# p4b-leds.net
KiCad netlist of a schematic drawn in Altium Designer
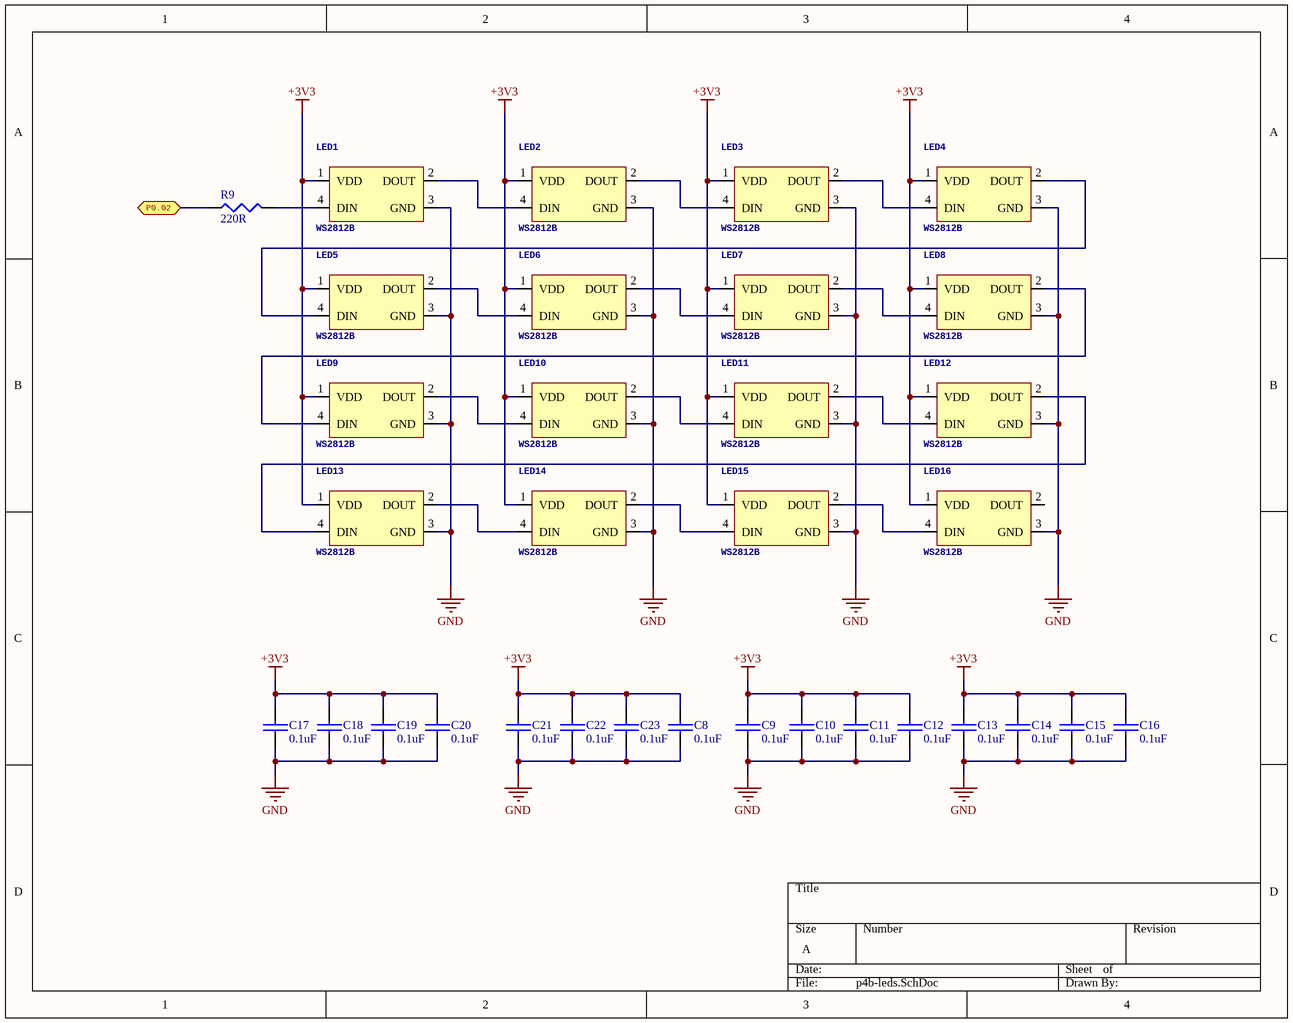
[diagram p0: p4b-leds.SchDoc]

(export (version "E")
  (design (tool "Eeschema 10.0.6"))
  (components
    (comp (ref "C8")
      (value "0.1uF")
      (footprint "C0603")
      (description "CAP, CER, 0.1UF, 6.3v, 10%, X5R, 0603")
      (fields (field (name "Comment") "VALUE"))
      (libsource (lib "bdk-schlib") (part "CAP-0.1UF-0603"))
    )
    (comp (ref "C9")
      (value "0.1uF")
      (footprint "C0603")
      (description "CAP, CER, 0.1UF, 6.3v, 10%, X5R, 0603")
      (fields (field (name "Comment") "VALUE"))
      (libsource (lib "bdk-schlib") (part "CAP-0.1UF-0603"))
    )
    (comp (ref "C10")
      (value "0.1uF")
      (footprint "C0603")
      (description "CAP, CER, 0.1UF, 6.3v, 10%, X5R, 0603")
      (fields (field (name "Comment") "VALUE"))
      (libsource (lib "bdk-schlib") (part "CAP-0.1UF-0603"))
    )
    (comp (ref "C11")
      (value "0.1uF")
      (footprint "C0603")
      (description "CAP, CER, 0.1UF, 6.3v, 10%, X5R, 0603")
      (fields (field (name "Comment") "VALUE"))
      (libsource (lib "bdk-schlib") (part "CAP-0.1UF-0603"))
    )
    (comp (ref "C12")
      (value "0.1uF")
      (footprint "C0603")
      (description "CAP, CER, 0.1UF, 6.3v, 10%, X5R, 0603")
      (fields (field (name "Comment") "VALUE"))
      (libsource (lib "bdk-schlib") (part "CAP-0.1UF-0603"))
    )
    (comp (ref "C13")
      (value "0.1uF")
      (footprint "C0603")
      (description "CAP, CER, 0.1UF, 6.3v, 10%, X5R, 0603")
      (fields (field (name "Comment") "VALUE"))
      (libsource (lib "bdk-schlib") (part "CAP-0.1UF-0603"))
    )
    (comp (ref "C14")
      (value "0.1uF")
      (footprint "C0603")
      (description "CAP, CER, 0.1UF, 6.3v, 10%, X5R, 0603")
      (fields (field (name "Comment") "VALUE"))
      (libsource (lib "bdk-schlib") (part "CAP-0.1UF-0603"))
    )
    (comp (ref "C15")
      (value "0.1uF")
      (footprint "C0603")
      (description "CAP, CER, 0.1UF, 6.3v, 10%, X5R, 0603")
      (fields (field (name "Comment") "VALUE"))
      (libsource (lib "bdk-schlib") (part "CAP-0.1UF-0603"))
    )
    (comp (ref "C16")
      (value "0.1uF")
      (footprint "C0603")
      (description "CAP, CER, 0.1UF, 6.3v, 10%, X5R, 0603")
      (fields (field (name "Comment") "VALUE"))
      (libsource (lib "bdk-schlib") (part "CAP-0.1UF-0603"))
    )
    (comp (ref "C17")
      (value "0.1uF")
      (footprint "C0603")
      (description "CAP, CER, 0.1UF, 6.3v, 10%, X5R, 0603")
      (fields (field (name "Comment") "VALUE"))
      (libsource (lib "bdk-schlib") (part "CAP-0.1UF-0603"))
    )
    (comp (ref "C18")
      (value "0.1uF")
      (footprint "C0603")
      (description "CAP, CER, 0.1UF, 6.3v, 10%, X5R, 0603")
      (fields (field (name "Comment") "VALUE"))
      (libsource (lib "bdk-schlib") (part "CAP-0.1UF-0603"))
    )
    (comp (ref "C19")
      (value "0.1uF")
      (footprint "C0603")
      (description "CAP, CER, 0.1UF, 6.3v, 10%, X5R, 0603")
      (fields (field (name "Comment") "VALUE"))
      (libsource (lib "bdk-schlib") (part "CAP-0.1UF-0603"))
    )
    (comp (ref "C20")
      (value "0.1uF")
      (footprint "C0603")
      (description "CAP, CER, 0.1UF, 6.3v, 10%, X5R, 0603")
      (fields (field (name "Comment") "VALUE"))
      (libsource (lib "bdk-schlib") (part "CAP-0.1UF-0603"))
    )
    (comp (ref "C21")
      (value "0.1uF")
      (footprint "C0603")
      (description "CAP, CER, 0.1UF, 6.3v, 10%, X5R, 0603")
      (fields (field (name "Comment") "VALUE"))
      (libsource (lib "bdk-schlib") (part "CAP-0.1UF-0603"))
    )
    (comp (ref "C22")
      (value "0.1uF")
      (footprint "C0603")
      (description "CAP, CER, 0.1UF, 6.3v, 10%, X5R, 0603")
      (fields (field (name "Comment") "VALUE"))
      (libsource (lib "bdk-schlib") (part "CAP-0.1UF-0603"))
    )
    (comp (ref "C23")
      (value "0.1uF")
      (footprint "C0603")
      (description "CAP, CER, 0.1UF, 6.3v, 10%, X5R, 0603")
      (fields (field (name "Comment") "VALUE"))
      (libsource (lib "bdk-schlib") (part "CAP-0.1UF-0603"))
    )
    (comp (ref "LED1")
      (value "WS2812B")
      (footprint "WS2812B")
      (description "WS2812B RGB LED")
      (libsource (lib "bdk-schlib") (part "WS2812B"))
    )
    (comp (ref "LED2")
      (value "WS2812B")
      (footprint "WS2812B")
      (description "WS2812B RGB LED")
      (libsource (lib "bdk-schlib") (part "WS2812B"))
    )
    (comp (ref "LED3")
      (value "WS2812B")
      (footprint "WS2812B")
      (description "WS2812B RGB LED")
      (libsource (lib "bdk-schlib") (part "WS2812B"))
    )
    (comp (ref "LED4")
      (value "WS2812B")
      (footprint "WS2812B")
      (description "WS2812B RGB LED")
      (libsource (lib "bdk-schlib") (part "WS2812B"))
    )
    (comp (ref "LED5")
      (value "WS2812B")
      (footprint "WS2812B")
      (description "WS2812B RGB LED")
      (libsource (lib "bdk-schlib") (part "WS2812B"))
    )
    (comp (ref "LED6")
      (value "WS2812B")
      (footprint "WS2812B")
      (description "WS2812B RGB LED")
      (libsource (lib "bdk-schlib") (part "WS2812B"))
    )
    (comp (ref "LED7")
      (value "WS2812B")
      (footprint "WS2812B")
      (description "WS2812B RGB LED")
      (libsource (lib "bdk-schlib") (part "WS2812B"))
    )
    (comp (ref "LED8")
      (value "WS2812B")
      (footprint "WS2812B")
      (description "WS2812B RGB LED")
      (libsource (lib "bdk-schlib") (part "WS2812B"))
    )
    (comp (ref "LED9")
      (value "WS2812B")
      (footprint "WS2812B")
      (description "WS2812B RGB LED")
      (libsource (lib "bdk-schlib") (part "WS2812B"))
    )
    (comp (ref "LED10")
      (value "WS2812B")
      (footprint "WS2812B")
      (description "WS2812B RGB LED")
      (libsource (lib "bdk-schlib") (part "WS2812B"))
    )
    (comp (ref "LED11")
      (value "WS2812B")
      (footprint "WS2812B")
      (description "WS2812B RGB LED")
      (libsource (lib "bdk-schlib") (part "WS2812B"))
    )
    (comp (ref "LED12")
      (value "WS2812B")
      (footprint "WS2812B")
      (description "WS2812B RGB LED")
      (libsource (lib "bdk-schlib") (part "WS2812B"))
    )
    (comp (ref "LED13")
      (value "WS2812B")
      (footprint "WS2812B")
      (description "WS2812B RGB LED")
      (libsource (lib "bdk-schlib") (part "WS2812B"))
    )
    (comp (ref "LED14")
      (value "WS2812B")
      (footprint "WS2812B")
      (description "WS2812B RGB LED")
      (libsource (lib "bdk-schlib") (part "WS2812B"))
    )
    (comp (ref "LED15")
      (value "WS2812B")
      (footprint "WS2812B")
      (description "WS2812B RGB LED")
      (libsource (lib "bdk-schlib") (part "WS2812B"))
    )
    (comp (ref "LED16")
      (value "WS2812B")
      (footprint "WS2812B")
      (description "WS2812B RGB LED")
      (libsource (lib "bdk-schlib") (part "WS2812B"))
    )
    (comp (ref "R9")
      (value "220R")
      (footprint "R0603")
      (description "RES, 220 OHM, 1/10W, 5%, 0603 SMD")
      (libsource (lib "bdk-schlib") (part "RES-47-0603"))
    )
  )
  (nets
    (net (code "1") (name "+3V3") (class "Default")
      (node (ref "C10") (pin "1") (pinfunction "A_1") (pintype "passive"))
      (node (ref "C11") (pin "1") (pinfunction "A_1") (pintype "passive"))
      (node (ref "C12") (pin "1") (pinfunction "A_1") (pintype "passive"))
      (node (ref "C13") (pin "1") (pinfunction "A_1") (pintype "passive"))
      (node (ref "C14") (pin "1") (pinfunction "A_1") (pintype "passive"))
      (node (ref "C15") (pin "1") (pinfunction "A_1") (pintype "passive"))
      (node (ref "C16") (pin "1") (pinfunction "A_1") (pintype "passive"))
      (node (ref "C17") (pin "1") (pinfunction "A_1") (pintype "passive"))
      (node (ref "C18") (pin "1") (pinfunction "A_1") (pintype "passive"))
      (node (ref "C19") (pin "1") (pinfunction "A_1") (pintype "passive"))
      (node (ref "C20") (pin "1") (pinfunction "A_1") (pintype "passive"))
      (node (ref "C21") (pin "1") (pinfunction "A_1") (pintype "passive"))
      (node (ref "C22") (pin "1") (pinfunction "A_1") (pintype "passive"))
      (node (ref "C23") (pin "1") (pinfunction "A_1") (pintype "passive"))
      (node (ref "C8") (pin "1") (pinfunction "A_1") (pintype "passive"))
      (node (ref "C9") (pin "1") (pinfunction "A_1") (pintype "passive"))
      (node (ref "LED1") (pin "1") (pinfunction "VDD_1") (pintype "passive"))
      (node (ref "LED10") (pin "1") (pinfunction "VDD_1") (pintype "passive"))
      (node (ref "LED11") (pin "1") (pinfunction "VDD_1") (pintype "passive"))
      (node (ref "LED12") (pin "1") (pinfunction "VDD_1") (pintype "passive"))
      (node (ref "LED13") (pin "1") (pinfunction "VDD_1") (pintype "passive"))
      (node (ref "LED14") (pin "1") (pinfunction "VDD_1") (pintype "passive"))
      (node (ref "LED15") (pin "1") (pinfunction "VDD_1") (pintype "passive"))
      (node (ref "LED16") (pin "1") (pinfunction "VDD_1") (pintype "passive"))
      (node (ref "LED2") (pin "1") (pinfunction "VDD_1") (pintype "passive"))
      (node (ref "LED3") (pin "1") (pinfunction "VDD_1") (pintype "passive"))
      (node (ref "LED4") (pin "1") (pinfunction "VDD_1") (pintype "passive"))
      (node (ref "LED5") (pin "1") (pinfunction "VDD_1") (pintype "passive"))
      (node (ref "LED6") (pin "1") (pinfunction "VDD_1") (pintype "passive"))
      (node (ref "LED7") (pin "1") (pinfunction "VDD_1") (pintype "passive"))
      (node (ref "LED8") (pin "1") (pinfunction "VDD_1") (pintype "passive"))
      (node (ref "LED9") (pin "1") (pinfunction "VDD_1") (pintype "passive"))
    )
    (net (code "2") (name "/P0.02") (class "Default")
      (node (ref "R9") (pin "1") (pinfunction "A_1") (pintype "passive"))
    )
    (net (code "3") (name "GND") (class "Default")
      (node (ref "C10") (pin "2") (pinfunction "B_2") (pintype "passive"))
      (node (ref "C11") (pin "2") (pinfunction "B_2") (pintype "passive"))
      (node (ref "C12") (pin "2") (pinfunction "B_2") (pintype "passive"))
      (node (ref "C13") (pin "2") (pinfunction "B_2") (pintype "passive"))
      (node (ref "C14") (pin "2") (pinfunction "B_2") (pintype "passive"))
      (node (ref "C15") (pin "2") (pinfunction "B_2") (pintype "passive"))
      (node (ref "C16") (pin "2") (pinfunction "B_2") (pintype "passive"))
      (node (ref "C17") (pin "2") (pinfunction "B_2") (pintype "passive"))
      (node (ref "C18") (pin "2") (pinfunction "B_2") (pintype "passive"))
      (node (ref "C19") (pin "2") (pinfunction "B_2") (pintype "passive"))
      (node (ref "C20") (pin "2") (pinfunction "B_2") (pintype "passive"))
      (node (ref "C21") (pin "2") (pinfunction "B_2") (pintype "passive"))
      (node (ref "C22") (pin "2") (pinfunction "B_2") (pintype "passive"))
      (node (ref "C23") (pin "2") (pinfunction "B_2") (pintype "passive"))
      (node (ref "C8") (pin "2") (pinfunction "B_2") (pintype "passive"))
      (node (ref "C9") (pin "2") (pinfunction "B_2") (pintype "passive"))
      (node (ref "LED1") (pin "3") (pinfunction "GND_3") (pintype "passive"))
      (node (ref "LED10") (pin "3") (pinfunction "GND_3") (pintype "passive"))
      (node (ref "LED11") (pin "3") (pinfunction "GND_3") (pintype "passive"))
      (node (ref "LED12") (pin "3") (pinfunction "GND_3") (pintype "passive"))
      (node (ref "LED13") (pin "3") (pinfunction "GND_3") (pintype "passive"))
      (node (ref "LED14") (pin "3") (pinfunction "GND_3") (pintype "passive"))
      (node (ref "LED15") (pin "3") (pinfunction "GND_3") (pintype "passive"))
      (node (ref "LED16") (pin "3") (pinfunction "GND_3") (pintype "passive"))
      (node (ref "LED2") (pin "3") (pinfunction "GND_3") (pintype "passive"))
      (node (ref "LED3") (pin "3") (pinfunction "GND_3") (pintype "passive"))
      (node (ref "LED4") (pin "3") (pinfunction "GND_3") (pintype "passive"))
      (node (ref "LED5") (pin "3") (pinfunction "GND_3") (pintype "passive"))
      (node (ref "LED6") (pin "3") (pinfunction "GND_3") (pintype "passive"))
      (node (ref "LED7") (pin "3") (pinfunction "GND_3") (pintype "passive"))
      (node (ref "LED8") (pin "3") (pinfunction "GND_3") (pintype "passive"))
      (node (ref "LED9") (pin "3") (pinfunction "GND_3") (pintype "passive"))
    )
    (net (code "4") (name "Net-(LED1-DIN)") (class "Default")
      (node (ref "LED1") (pin "4") (pinfunction "DIN_4") (pintype "passive"))
      (node (ref "R9") (pin "2") (pinfunction "B_2") (pintype "passive"))
    )
    (net (code "5") (name "Net-(LED1-DOUT)") (class "Default")
      (node (ref "LED1") (pin "2") (pinfunction "DOUT_2") (pintype "passive"))
      (node (ref "LED2") (pin "4") (pinfunction "DIN_4") (pintype "passive"))
    )
    (net (code "6") (name "Net-(LED2-DOUT)") (class "Default")
      (node (ref "LED2") (pin "2") (pinfunction "DOUT_2") (pintype "passive"))
      (node (ref "LED3") (pin "4") (pinfunction "DIN_4") (pintype "passive"))
    )
    (net (code "7") (name "Net-(LED3-DOUT)") (class "Default")
      (node (ref "LED3") (pin "2") (pinfunction "DOUT_2") (pintype "passive"))
      (node (ref "LED4") (pin "4") (pinfunction "DIN_4") (pintype "passive"))
    )
    (net (code "8") (name "Net-(LED4-DOUT)") (class "Default")
      (node (ref "LED4") (pin "2") (pinfunction "DOUT_2") (pintype "passive"))
      (node (ref "LED5") (pin "4") (pinfunction "DIN_4") (pintype "passive"))
    )
    (net (code "9") (name "Net-(LED5-DOUT)") (class "Default")
      (node (ref "LED5") (pin "2") (pinfunction "DOUT_2") (pintype "passive"))
      (node (ref "LED6") (pin "4") (pinfunction "DIN_4") (pintype "passive"))
    )
    (net (code "10") (name "Net-(LED6-DOUT)") (class "Default")
      (node (ref "LED6") (pin "2") (pinfunction "DOUT_2") (pintype "passive"))
      (node (ref "LED7") (pin "4") (pinfunction "DIN_4") (pintype "passive"))
    )
    (net (code "11") (name "Net-(LED7-DOUT)") (class "Default")
      (node (ref "LED7") (pin "2") (pinfunction "DOUT_2") (pintype "passive"))
      (node (ref "LED8") (pin "4") (pinfunction "DIN_4") (pintype "passive"))
    )
    (net (code "12") (name "Net-(LED8-DOUT)") (class "Default")
      (node (ref "LED8") (pin "2") (pinfunction "DOUT_2") (pintype "passive"))
      (node (ref "LED9") (pin "4") (pinfunction "DIN_4") (pintype "passive"))
    )
    (net (code "13") (name "Net-(LED10-DIN)") (class "Default")
      (node (ref "LED10") (pin "4") (pinfunction "DIN_4") (pintype "passive"))
      (node (ref "LED9") (pin "2") (pinfunction "DOUT_2") (pintype "passive"))
    )
    (net (code "14") (name "Net-(LED10-DOUT)") (class "Default")
      (node (ref "LED10") (pin "2") (pinfunction "DOUT_2") (pintype "passive"))
      (node (ref "LED11") (pin "4") (pinfunction "DIN_4") (pintype "passive"))
    )
    (net (code "15") (name "Net-(LED11-DOUT)") (class "Default")
      (node (ref "LED11") (pin "2") (pinfunction "DOUT_2") (pintype "passive"))
      (node (ref "LED12") (pin "4") (pinfunction "DIN_4") (pintype "passive"))
    )
    (net (code "16") (name "Net-(LED12-DOUT)") (class "Default")
      (node (ref "LED12") (pin "2") (pinfunction "DOUT_2") (pintype "passive"))
      (node (ref "LED13") (pin "4") (pinfunction "DIN_4") (pintype "passive"))
    )
    (net (code "17") (name "Net-(LED13-DOUT)") (class "Default")
      (node (ref "LED13") (pin "2") (pinfunction "DOUT_2") (pintype "passive"))
      (node (ref "LED14") (pin "4") (pinfunction "DIN_4") (pintype "passive"))
    )
    (net (code "18") (name "Net-(LED14-DOUT)") (class "Default")
      (node (ref "LED14") (pin "2") (pinfunction "DOUT_2") (pintype "passive"))
      (node (ref "LED15") (pin "4") (pinfunction "DIN_4") (pintype "passive"))
    )
    (net (code "19") (name "Net-(LED15-DOUT)") (class "Default")
      (node (ref "LED15") (pin "2") (pinfunction "DOUT_2") (pintype "passive"))
      (node (ref "LED16") (pin "4") (pinfunction "DIN_4") (pintype "passive"))
    )
    (net (code "20") (name "unconnected-(LED16-DOUT-Pad2)") (class "Default")
      (node (ref "LED16") (pin "2") (pinfunction "DOUT_2") (pintype "passive"))
    )
  )
)
